# B_D_PFC.net
KiCad netlist of a schematic drawn in Altium Designer
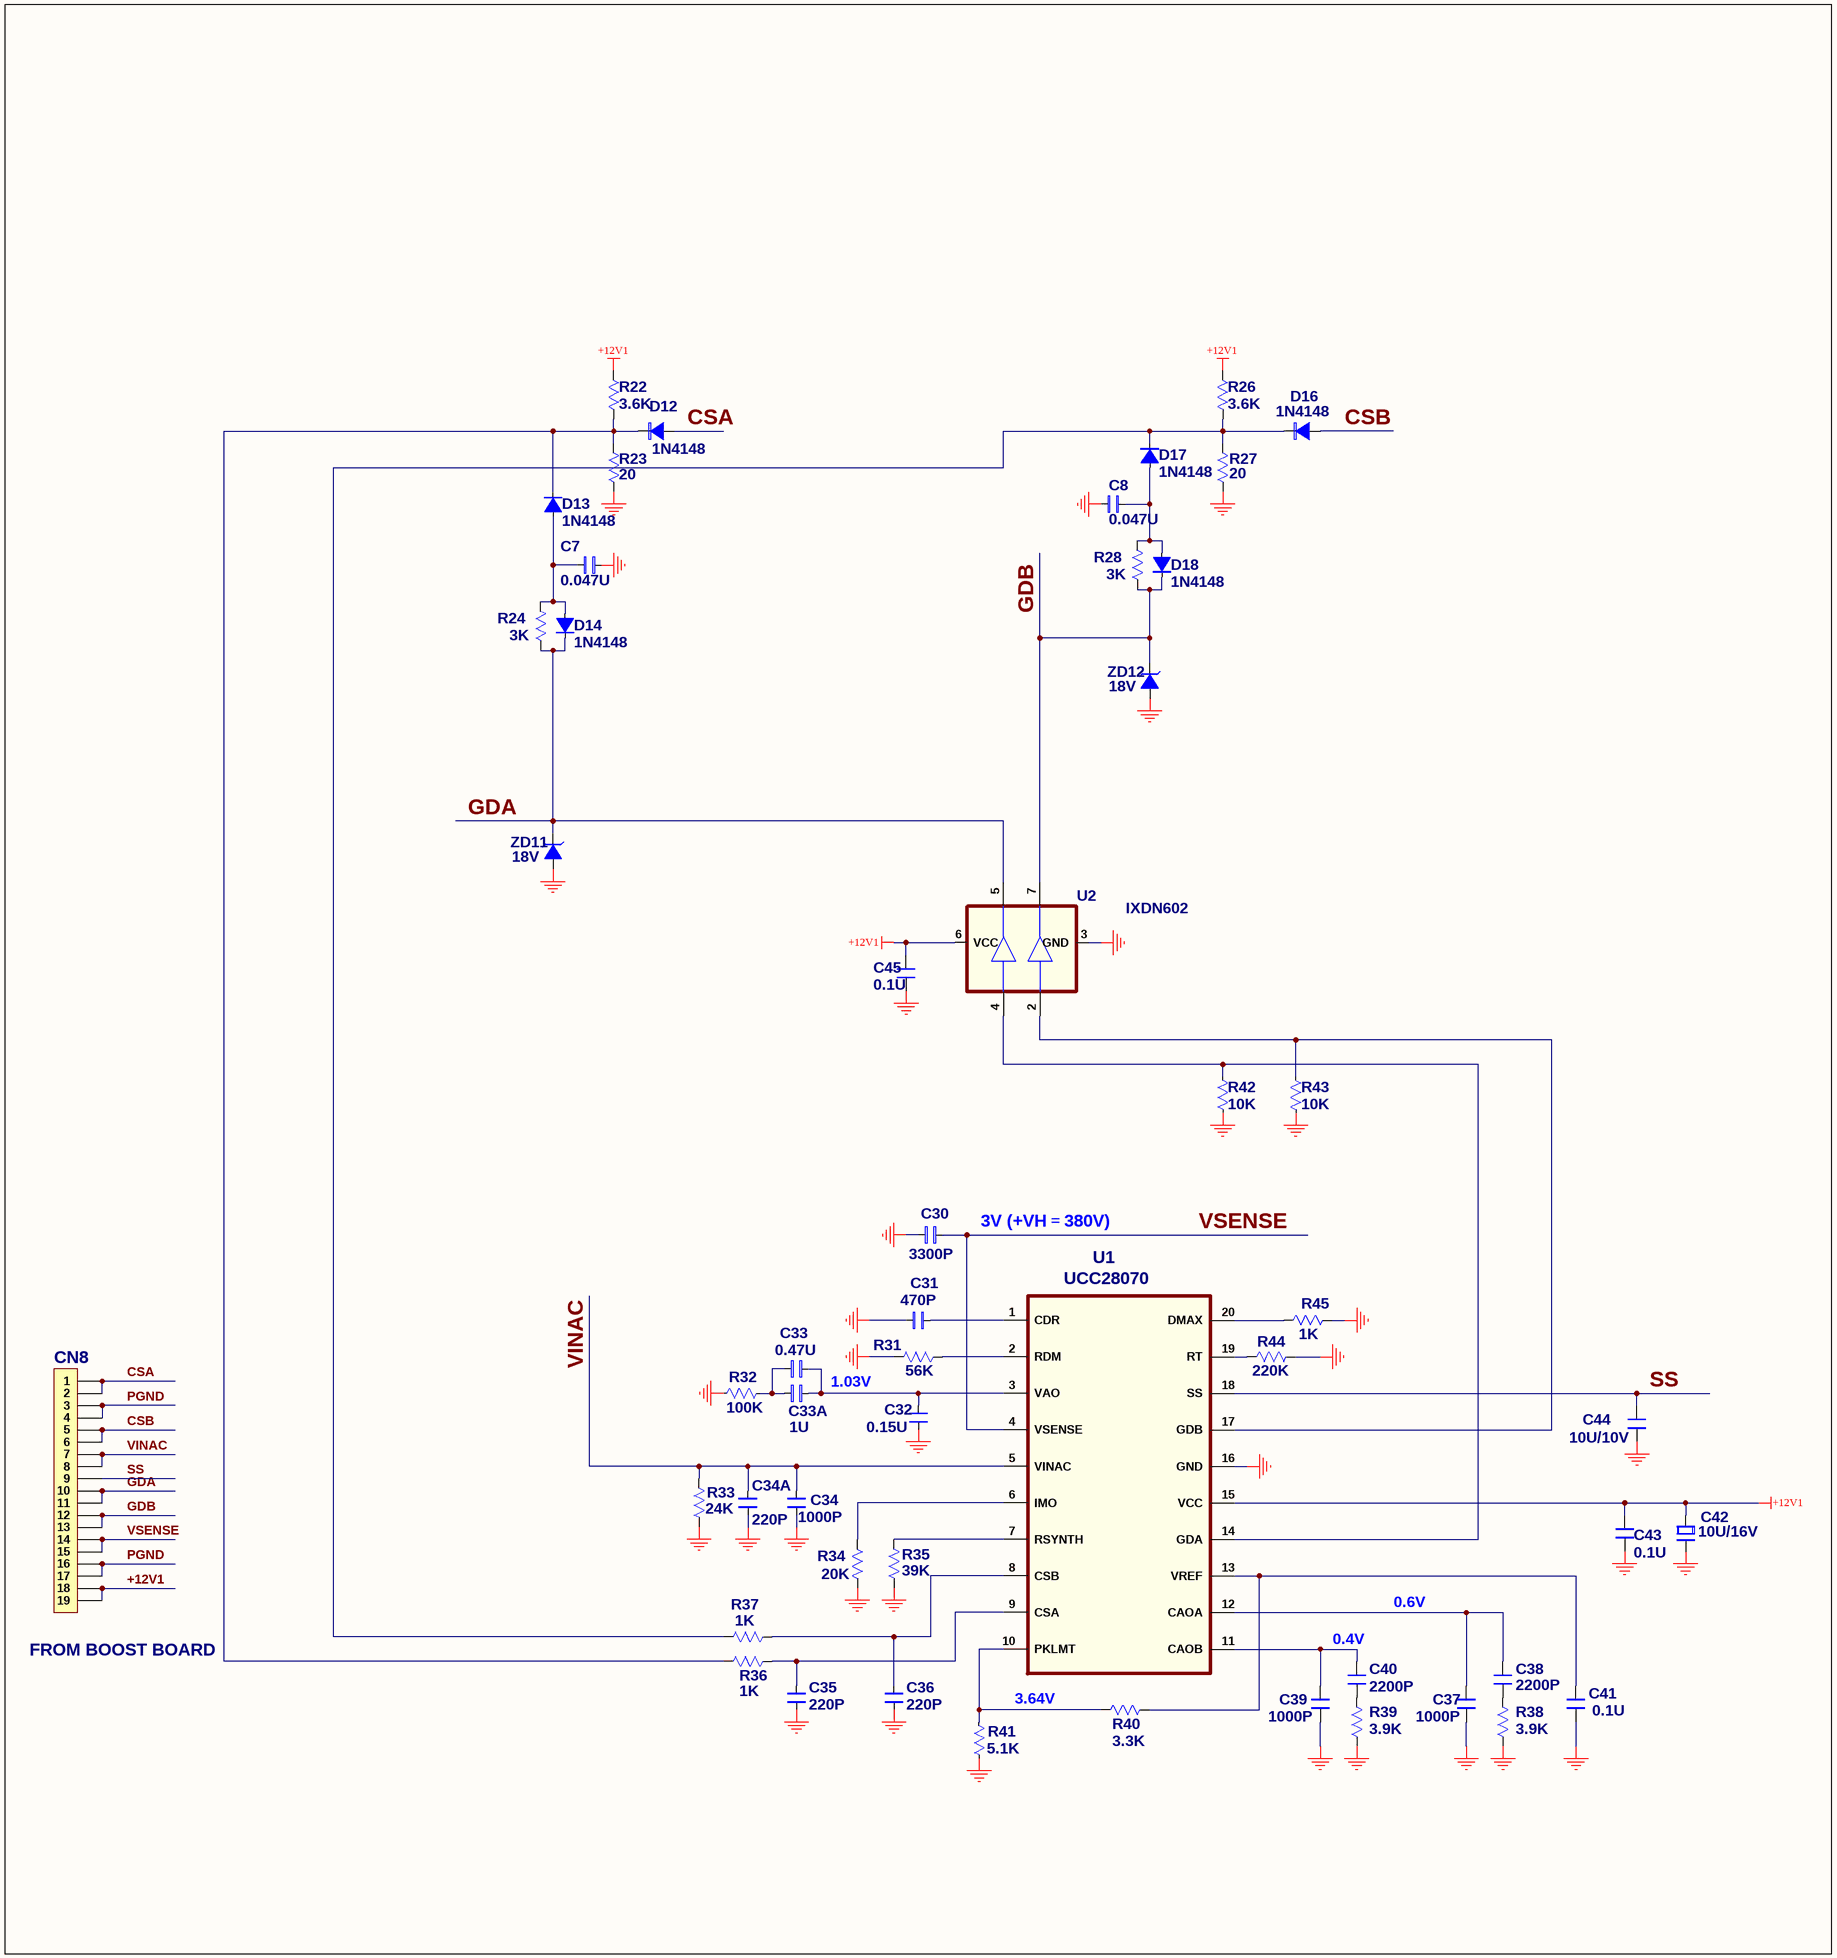
[diagram p0: B&D PFC.SchDoc]

(export (version "E")
  (design (tool "Eeschema 10.0.6"))
  (components
    (comp (ref "C7")
      (value "0.047U")
      (footprint "2012(0805)-2.54")
      (description "Capacitor")
      (libsource (lib "*") (part "CAP_2"))
    )
    (comp (ref "C8")
      (value "0.047U")
      (footprint "2012(0805)-2.54")
      (description "Capacitor")
      (libsource (lib "*") (part "CAP_2"))
    )
    (comp (ref "C30")
      (value "3300P")
      (footprint "2012(0805)-2.54")
      (description "Capacitor")
      (libsource (lib "*") (part "CAP_2"))
    )
    (comp (ref "C31")
      (value "470P")
      (footprint "2012(0805)-2.54")
      (description "Capacitor")
      (libsource (lib "*") (part "CAP_2"))
    )
    (comp (ref "C32")
      (value "0.15U")
      (footprint "2012(0805)-2.54")
      (description "Capacitor")
      (libsource (lib "*") (part "CAP_2"))
    )
    (comp (ref "C33")
      (value "0.47U")
      (footprint "2012(0805)-2.54")
      (description "Capacitor")
      (libsource (lib "*") (part "CAP_2"))
    )
    (comp (ref "C33A")
      (value "1U")
      (footprint "2012(0805)-2.54")
      (description "Capacitor")
      (libsource (lib "*") (part "CAP_2"))
    )
    (comp (ref "C34")
      (value "1000P")
      (footprint "2012(0805)-2.54")
      (description "Capacitor")
      (libsource (lib "*") (part "CAP_2"))
    )
    (comp (ref "C34A")
      (value "220P")
      (footprint "2012(0805)-2.54")
      (description "Capacitor")
      (libsource (lib "*") (part "CAP_2"))
    )
    (comp (ref "C35")
      (value "220P")
      (footprint "2012(0805)-2.54")
      (description "Capacitor")
      (libsource (lib "*") (part "CAP_2"))
    )
    (comp (ref "C36")
      (value "220P")
      (footprint "2012(0805)-2.54")
      (description "Capacitor")
      (libsource (lib "*") (part "CAP_2"))
    )
    (comp (ref "C37")
      (value "1000P")
      (footprint "2012(0805)-2.54")
      (description "Capacitor")
      (libsource (lib "*") (part "CAP_3"))
    )
    (comp (ref "C38")
      (value "2200P")
      (footprint "2012(0805)-2.54")
      (description "Capacitor")
      (libsource (lib "*") (part "CAP_3"))
    )
    (comp (ref "C39")
      (value "1000P")
      (footprint "2012(0805)-2.54")
      (description "Capacitor")
      (libsource (lib "*") (part "CAP_3"))
    )
    (comp (ref "C40")
      (value "2200P")
      (footprint "2012(0805)-2.54")
      (description "Capacitor")
      (libsource (lib "*") (part "CAP_3"))
    )
    (comp (ref "C41")
      (value "0.1U")
      (footprint "2012(0805)-2.54")
      (description "Capacitor")
      (libsource (lib "*") (part "CAP_3"))
    )
    (comp (ref "C42")
      (value "10U/16V")
      (footprint "CAP P 3528")
      (description "Electrolytic Capacitor")
      (libsource (lib "*") (part "CAP P_3"))
    )
    (comp (ref "C43")
      (value "0.1U")
      (footprint "2012(0805)-2.54")
      (description "Capacitor")
      (libsource (lib "*") (part "CAP_3"))
    )
    (comp (ref "C44")
      (value "10U/10V")
      (footprint "3216(1206)-3.05")
      (description "Capacitor")
      (libsource (lib "*") (part "CAP_3"))
    )
    (comp (ref "C45")
      (value "0.1U")
      (footprint "2012(0805)-2.54")
      (description "Capacitor")
      (libsource (lib "*") (part "CAP_3"))
    )
    (comp (ref "CN8")
      (value "PIN HDR 1*19-90")
      (footprint "PIN HDR 1*19-90")
      (description "Connector")
      (libsource (lib "*") (part "CON19"))
    )
    (comp (ref "D12")
      (value "1N4148")
      (footprint "D3515")
      (description "Diode")
      (libsource (lib "*") (part "DIODE(AK)_2"))
    )
    (comp (ref "D13")
      (value "1N4148")
      (footprint "D3515")
      (description "Diode")
      (libsource (lib "*") (part "DIODE(AK)_1"))
    )
    (comp (ref "D14")
      (value "1N4148")
      (footprint "D3515")
      (description "Diode")
      (libsource (lib "*") (part "DIODE(AK)_1"))
    )
    (comp (ref "D16")
      (value "1N4148")
      (footprint "D3515")
      (description "Diode")
      (libsource (lib "*") (part "DIODE(AK)_2"))
    )
    (comp (ref "D17")
      (value "1N4148")
      (footprint "D3515")
      (description "Diode")
      (libsource (lib "*") (part "DIODE(AK)_1"))
    )
    (comp (ref "D18")
      (value "1N4148")
      (footprint "D3515")
      (description "Diode")
      (libsource (lib "*") (part "DIODE(AK)_1"))
    )
    (comp (ref "R22")
      (value "3.6K")
      (footprint "2012(0805)-2.54")
      (description "Resistor")
      (libsource (lib "*") (part "RES_2"))
    )
    (comp (ref "R23")
      (value "20")
      (footprint "2012(0805)-2.54")
      (description "Resistor")
      (libsource (lib "*") (part "RES_2"))
    )
    (comp (ref "R24")
      (value "3K")
      (footprint "2012(0805)-2.54")
      (description "Resistor")
      (libsource (lib "*") (part "RES_2"))
    )
    (comp (ref "R26")
      (value "3.6K")
      (footprint "2012(0805)-2.54")
      (description "Resistor")
      (libsource (lib "*") (part "RES_2"))
    )
    (comp (ref "R27")
      (value "20")
      (footprint "2012(0805)-2.54")
      (description "Resistor")
      (libsource (lib "*") (part "RES_2"))
    )
    (comp (ref "R28")
      (value "3K")
      (footprint "2012(0805)-2.54")
      (description "Resistor")
      (libsource (lib "*") (part "RES_2"))
    )
    (comp (ref "R31")
      (value "56K")
      (footprint "2012(0805)-2.54")
      (description "Resistor")
      (libsource (lib "*") (part "RES_2"))
    )
    (comp (ref "R32")
      (value "100K")
      (footprint "2012(0805)-2.54")
      (description "Resistor")
      (libsource (lib "*") (part "RES_1"))
    )
    (comp (ref "R33")
      (value "24K")
      (footprint "2012(0805)-2.54")
      (description "Resistor")
      (libsource (lib "*") (part "RES_2"))
    )
    (comp (ref "R34")
      (value "20K")
      (footprint "2012(0805)-2.54")
      (description "Resistor")
      (libsource (lib "*") (part "RES_2"))
    )
    (comp (ref "R35")
      (value "39K")
      (footprint "2012(0805)-2.54")
      (description "Resistor")
      (libsource (lib "*") (part "RES_2"))
    )
    (comp (ref "R36")
      (value "1K")
      (footprint "2012(0805)-2.54")
      (description "Resistor")
      (libsource (lib "*") (part "RES_2"))
    )
    (comp (ref "R37")
      (value "1K")
      (footprint "2012(0805)-2.54")
      (description "Resistor")
      (libsource (lib "*") (part "RES_2"))
    )
    (comp (ref "R38")
      (value "3.9K")
      (footprint "2012(0805)-2.54")
      (description "Resistor")
      (libsource (lib "*") (part "RES_2"))
    )
    (comp (ref "R39")
      (value "3.9K")
      (footprint "2012(0805)-2.54")
      (description "Resistor")
      (libsource (lib "*") (part "RES_2"))
    )
    (comp (ref "R40")
      (value "3.3K")
      (footprint "2012(0805)-2.54")
      (description "Resistor")
      (libsource (lib "*") (part "RES_2"))
    )
    (comp (ref "R41")
      (value "5.1K")
      (footprint "2012(0805)-2.54")
      (description "Resistor")
      (libsource (lib "*") (part "RES_1"))
    )
    (comp (ref "R42")
      (value "10K")
      (footprint "2012(0805)-2.54")
      (description "Resistor")
      (libsource (lib "*") (part "RES_1"))
    )
    (comp (ref "R43")
      (value "10K")
      (footprint "2012(0805)-2.54")
      (description "Resistor")
      (libsource (lib "*") (part "RES_1"))
    )
    (comp (ref "R44")
      (value "220K")
      (footprint "2012(0805)-2.54")
      (description "Resistor")
      (libsource (lib "*") (part "RES_2"))
    )
    (comp (ref "R45")
      (value "1K")
      (footprint "2012(0805)-2.54")
      (description "Resistor")
      (libsource (lib "*") (part "RES_2"))
    )
    (comp (ref "U1")
      (value "UCC28070")
      (footprint "TSSOP20-240-0.65")
      (libsource (lib "*") (part "UCC28070_1"))
    )
    (comp (ref "U2")
      (value "IXDN602")
      (footprint "SO8-240-1.27")
      (description "Ultrafast MOSFET Drivers")
      (libsource (lib "*") (part "IXDN602_3"))
    )
    (comp (ref "ZD11")
      (value "18V")
      (footprint "DZ3515-3.56")
      (description "Zener Diode")
      (libsource (lib "*") (part "ZD_2"))
    )
    (comp (ref "ZD12")
      (value "18V")
      (footprint "DZ3515-3.56")
      (description "Zener Diode")
      (libsource (lib "*") (part "ZD_2"))
    )
  )
  (nets
    (net (code "1") (name "+12V1") (class "Default")
      (node (ref "C42") (pin "1") (pinfunction "1_1") (pintype "passive"))
      (node (ref "C43") (pin "1") (pinfunction "1_1") (pintype "passive"))
      (node (ref "C45") (pin "1") (pinfunction "1_1") (pintype "passive"))
      (node (ref "CN8") (pin "18") (pinfunction "18_18") (pintype "passive"))
      (node (ref "CN8") (pin "19") (pinfunction "19_19") (pintype "passive"))
      (node (ref "R22") (pin "1") (pinfunction "1_1") (pintype "passive"))
      (node (ref "R26") (pin "1") (pinfunction "1_1") (pintype "passive"))
      (node (ref "U1") (pin "15") (pinfunction "VCC_15") (pintype "passive"))
      (node (ref "U2") (pin "6") (pinfunction "VCC_6") (pintype "passive"))
    )
    (net (code "2") (name "/CSA") (class "Default")
      (node (ref "CN8") (pin "1") (pinfunction "1_1") (pintype "passive"))
      (node (ref "CN8") (pin "2") (pinfunction "2_2") (pintype "passive"))
      (node (ref "D12") (pin "1") (pinfunction "A_1") (pintype "passive"))
    )
    (net (code "3") (name "/CSB") (class "Default")
      (node (ref "CN8") (pin "5") (pinfunction "5_5") (pintype "passive"))
      (node (ref "CN8") (pin "6") (pinfunction "6_6") (pintype "passive"))
      (node (ref "D16") (pin "1") (pinfunction "A_1") (pintype "passive"))
    )
    (net (code "4") (name "/GDA") (class "Default")
      (node (ref "CN8") (pin "10") (pinfunction "10_10") (pintype "passive"))
      (node (ref "CN8") (pin "11") (pinfunction "11_11") (pintype "passive"))
      (node (ref "D14") (pin "2") (pinfunction "K_2") (pintype "passive"))
      (node (ref "R24") (pin "1") (pinfunction "1_1") (pintype "passive"))
      (node (ref "U2") (pin "5") (pinfunction "OUTB_5") (pintype "passive"))
      (node (ref "ZD11") (pin "2") (pinfunction "K_2") (pintype "passive"))
    )
    (net (code "5") (name "/GDB") (class "Default")
      (node (ref "CN8") (pin "12") (pinfunction "12_12") (pintype "passive"))
      (node (ref "CN8") (pin "13") (pinfunction "13_13") (pintype "passive"))
      (node (ref "D18") (pin "2") (pinfunction "K_2") (pintype "passive"))
      (node (ref "R28") (pin "1") (pinfunction "1_1") (pintype "passive"))
      (node (ref "U2") (pin "7") (pinfunction "OUTA_7") (pintype "passive"))
      (node (ref "ZD12") (pin "2") (pinfunction "K_2") (pintype "passive"))
    )
    (net (code "6") (name "/SS") (class "Default")
      (node (ref "C44") (pin "2") (pinfunction "2_2") (pintype "passive"))
      (node (ref "CN8") (pin "9") (pinfunction "9_9") (pintype "passive"))
      (node (ref "U1") (pin "18") (pinfunction "SS_18") (pintype "passive"))
    )
    (net (code "7") (name "/VINAC") (class "Default")
      (node (ref "C34") (pin "1") (pinfunction "1_1") (pintype "passive"))
      (node (ref "C34A") (pin "1") (pinfunction "1_1") (pintype "passive"))
      (node (ref "CN8") (pin "7") (pinfunction "7_7") (pintype "passive"))
      (node (ref "CN8") (pin "8") (pinfunction "8_8") (pintype "passive"))
      (node (ref "R33") (pin "2") (pinfunction "2_2") (pintype "passive"))
      (node (ref "U1") (pin "5") (pinfunction "VINAC_5") (pintype "passive"))
    )
    (net (code "8") (name "/VSENSE") (class "Default")
      (node (ref "C30") (pin "2") (pinfunction "2_2") (pintype "passive"))
      (node (ref "CN8") (pin "14") (pinfunction "14_14") (pintype "passive"))
      (node (ref "CN8") (pin "15") (pinfunction "15_15") (pintype "passive"))
      (node (ref "U1") (pin "4") (pinfunction "VSENSE_4") (pintype "passive"))
    )
    (net (code "9") (name "Net-(C33-Pad1)") (class "Default")
      (node (ref "C33") (pin "1") (pinfunction "1_1") (pintype "passive"))
      (node (ref "C33A") (pin "1") (pinfunction "1_1") (pintype "passive"))
      (node (ref "R32") (pin "2") (pinfunction "2_2") (pintype "passive"))
    )
    (net (code "10") (name "Net-(C38-Pad1)") (class "Default")
      (node (ref "C38") (pin "1") (pinfunction "1_1") (pintype "passive"))
      (node (ref "R38") (pin "2") (pinfunction "2_2") (pintype "passive"))
    )
    (net (code "11") (name "Net-(C40-Pad1)") (class "Default")
      (node (ref "C40") (pin "1") (pinfunction "1_1") (pintype "passive"))
      (node (ref "R39") (pin "2") (pinfunction "2_2") (pintype "passive"))
    )
    (net (code "12") (name "Net-(D12-K)") (class "Default")
      (node (ref "D12") (pin "2") (pinfunction "K_2") (pintype "passive"))
      (node (ref "D13") (pin "2") (pinfunction "K_2") (pintype "passive"))
      (node (ref "R22") (pin "2") (pinfunction "2_2") (pintype "passive"))
      (node (ref "R23") (pin "2") (pinfunction "2_2") (pintype "passive"))
      (node (ref "R36") (pin "2") (pinfunction "2_2") (pintype "passive"))
    )
    (net (code "13") (name "Net-(D13-A)") (class "Default")
      (node (ref "C7") (pin "1") (pinfunction "1_1") (pintype "passive"))
      (node (ref "D13") (pin "1") (pinfunction "A_1") (pintype "passive"))
      (node (ref "D14") (pin "1") (pinfunction "A_1") (pintype "passive"))
      (node (ref "R24") (pin "2") (pinfunction "2_2") (pintype "passive"))
    )
    (net (code "14") (name "Net-(D16-K)") (class "Default")
      (node (ref "D16") (pin "2") (pinfunction "K_2") (pintype "passive"))
      (node (ref "D17") (pin "2") (pinfunction "K_2") (pintype "passive"))
      (node (ref "R26") (pin "2") (pinfunction "2_2") (pintype "passive"))
      (node (ref "R27") (pin "2") (pinfunction "2_2") (pintype "passive"))
      (node (ref "R37") (pin "2") (pinfunction "2_2") (pintype "passive"))
    )
    (net (code "15") (name "Net-(D17-A)") (class "Default")
      (node (ref "C8") (pin "1") (pinfunction "1_1") (pintype "passive"))
      (node (ref "D17") (pin "1") (pinfunction "A_1") (pintype "passive"))
      (node (ref "D18") (pin "1") (pinfunction "A_1") (pintype "passive"))
      (node (ref "R28") (pin "2") (pinfunction "2_2") (pintype "passive"))
    )
    (net (code "16") (name "Net-(U1-CAOA)") (class "Default")
      (node (ref "C37") (pin "1") (pinfunction "1_1") (pintype "passive"))
      (node (ref "C38") (pin "2") (pinfunction "2_2") (pintype "passive"))
      (node (ref "U1") (pin "12") (pinfunction "CAOA_12") (pintype "passive"))
    )
    (net (code "17") (name "Net-(U1-CAOB)") (class "Default")
      (node (ref "C39") (pin "2") (pinfunction "2_2") (pintype "passive"))
      (node (ref "C40") (pin "2") (pinfunction "2_2") (pintype "passive"))
      (node (ref "U1") (pin "11") (pinfunction "CAOB_11") (pintype "passive"))
    )
    (net (code "18") (name "Net-(U1-CDR)") (class "Default")
      (node (ref "C31") (pin "2") (pinfunction "2_2") (pintype "passive"))
      (node (ref "U1") (pin "1") (pinfunction "CDR_1") (pintype "passive"))
    )
    (net (code "19") (name "Net-(U1-CSA)") (class "Default")
      (node (ref "C35") (pin "1") (pinfunction "1_1") (pintype "passive"))
      (node (ref "R36") (pin "1") (pinfunction "1_1") (pintype "passive"))
      (node (ref "U1") (pin "9") (pinfunction "CSA_9") (pintype "passive"))
    )
    (net (code "20") (name "Net-(U1-CSB)") (class "Default")
      (node (ref "C36") (pin "1") (pinfunction "1_1") (pintype "passive"))
      (node (ref "R37") (pin "1") (pinfunction "1_1") (pintype "passive"))
      (node (ref "U1") (pin "8") (pinfunction "CSB_8") (pintype "passive"))
    )
    (net (code "21") (name "Net-(U1-DMAX)") (class "Default")
      (node (ref "R45") (pin "1") (pinfunction "1_1") (pintype "passive"))
      (node (ref "U1") (pin "20") (pinfunction "DMAX_20") (pintype "passive"))
    )
    (net (code "22") (name "Net-(U1-GDA)") (class "Default")
      (node (ref "R42") (pin "2") (pinfunction "2_2") (pintype "passive"))
      (node (ref "U1") (pin "14") (pinfunction "GDA_14") (pintype "passive"))
      (node (ref "U2") (pin "4") (pinfunction "INB_4") (pintype "passive"))
    )
    (net (code "23") (name "Net-(U1-GDB)") (class "Default")
      (node (ref "R43") (pin "1") (pinfunction "1_1") (pintype "passive"))
      (node (ref "U1") (pin "17") (pinfunction "GDB_17") (pintype "passive"))
      (node (ref "U2") (pin "2") (pinfunction "INA_2") (pintype "passive"))
    )
    (net (code "24") (name "Net-(U1-IMO)") (class "Default")
      (node (ref "R34") (pin "1") (pinfunction "1_1") (pintype "passive"))
      (node (ref "U1") (pin "6") (pinfunction "IMO_6") (pintype "passive"))
    )
    (net (code "25") (name "Net-(U1-PKLMT)") (class "Default")
      (node (ref "R40") (pin "1") (pinfunction "1_1") (pintype "passive"))
      (node (ref "R41") (pin "2") (pinfunction "2_2") (pintype "passive"))
      (node (ref "U1") (pin "10") (pinfunction "PKLMT_10") (pintype "passive"))
    )
    (net (code "26") (name "Net-(U1-RDM)") (class "Default")
      (node (ref "R31") (pin "1") (pinfunction "1_1") (pintype "passive"))
      (node (ref "U1") (pin "2") (pinfunction "RDM_2") (pintype "passive"))
    )
    (net (code "27") (name "Net-(U1-RSYNTH)") (class "Default")
      (node (ref "R35") (pin "2") (pinfunction "2_2") (pintype "passive"))
      (node (ref "U1") (pin "7") (pinfunction "RSYNTH_7") (pintype "passive"))
    )
    (net (code "28") (name "Net-(U1-RT)") (class "Default")
      (node (ref "R44") (pin "1") (pinfunction "1_1") (pintype "passive"))
      (node (ref "U1") (pin "19") (pinfunction "RT_19") (pintype "passive"))
    )
    (net (code "29") (name "Net-(U1-VAO)") (class "Default")
      (node (ref "C32") (pin "2") (pinfunction "2_2") (pintype "passive"))
      (node (ref "C33") (pin "2") (pinfunction "2_2") (pintype "passive"))
      (node (ref "C33A") (pin "2") (pinfunction "2_2") (pintype "passive"))
      (node (ref "U1") (pin "3") (pinfunction "VAO_3") (pintype "passive"))
    )
    (net (code "30") (name "Net-(U1-VREF)") (class "Default")
      (node (ref "C41") (pin "2") (pinfunction "2_2") (pintype "passive"))
      (node (ref "R40") (pin "2") (pinfunction "2_2") (pintype "passive"))
      (node (ref "U1") (pin "13") (pinfunction "VREF_13") (pintype "passive"))
    )
    (net (code "31") (name "PGND") (class "Default")
      (node (ref "C30") (pin "1") (pinfunction "1_1") (pintype "passive"))
      (node (ref "C31") (pin "1") (pinfunction "1_1") (pintype "passive"))
      (node (ref "C32") (pin "1") (pinfunction "1_1") (pintype "passive"))
      (node (ref "C34") (pin "2") (pinfunction "2_2") (pintype "passive"))
      (node (ref "C34A") (pin "2") (pinfunction "2_2") (pintype "passive"))
      (node (ref "C35") (pin "2") (pinfunction "2_2") (pintype "passive"))
      (node (ref "C36") (pin "2") (pinfunction "2_2") (pintype "passive"))
      (node (ref "C37") (pin "2") (pinfunction "2_2") (pintype "passive"))
      (node (ref "C39") (pin "1") (pinfunction "1_1") (pintype "passive"))
      (node (ref "C41") (pin "1") (pinfunction "1_1") (pintype "passive"))
      (node (ref "C42") (pin "2") (pinfunction "2_2") (pintype "passive"))
      (node (ref "C43") (pin "2") (pinfunction "2_2") (pintype "passive"))
      (node (ref "C44") (pin "1") (pinfunction "1_1") (pintype "passive"))
      (node (ref "C45") (pin "2") (pinfunction "2_2") (pintype "passive"))
      (node (ref "C7") (pin "2") (pinfunction "2_2") (pintype "passive"))
      (node (ref "C8") (pin "2") (pinfunction "2_2") (pintype "passive"))
      (node (ref "CN8") (pin "16") (pinfunction "16_16") (pintype "passive"))
      (node (ref "CN8") (pin "17") (pinfunction "17_17") (pintype "passive"))
      (node (ref "CN8") (pin "3") (pinfunction "3_3") (pintype "passive"))
      (node (ref "CN8") (pin "4") (pinfunction "4_4") (pintype "passive"))
      (node (ref "R23") (pin "1") (pinfunction "1_1") (pintype "passive"))
      (node (ref "R27") (pin "1") (pinfunction "1_1") (pintype "passive"))
      (node (ref "R31") (pin "2") (pinfunction "2_2") (pintype "passive"))
      (node (ref "R32") (pin "1") (pinfunction "1_1") (pintype "passive"))
      (node (ref "R33") (pin "1") (pinfunction "1_1") (pintype "passive"))
      (node (ref "R34") (pin "2") (pinfunction "2_2") (pintype "passive"))
      (node (ref "R35") (pin "1") (pinfunction "1_1") (pintype "passive"))
      (node (ref "R38") (pin "1") (pinfunction "1_1") (pintype "passive"))
      (node (ref "R39") (pin "1") (pinfunction "1_1") (pintype "passive"))
      (node (ref "R41") (pin "1") (pinfunction "1_1") (pintype "passive"))
      (node (ref "R42") (pin "1") (pinfunction "1_1") (pintype "passive"))
      (node (ref "R43") (pin "2") (pinfunction "2_2") (pintype "passive"))
      (node (ref "R44") (pin "2") (pinfunction "2_2") (pintype "passive"))
      (node (ref "R45") (pin "2") (pinfunction "2_2") (pintype "passive"))
      (node (ref "U1") (pin "16") (pinfunction "GND_16") (pintype "passive"))
      (node (ref "U2") (pin "3") (pinfunction "GND_3") (pintype "passive"))
      (node (ref "ZD11") (pin "1") (pinfunction "A_1") (pintype "passive"))
      (node (ref "ZD12") (pin "1") (pinfunction "A_1") (pintype "passive"))
    )
  )
)
